# ESP32_adapter_revC.net
KiCad netlist of a schematic drawn in EAGLE
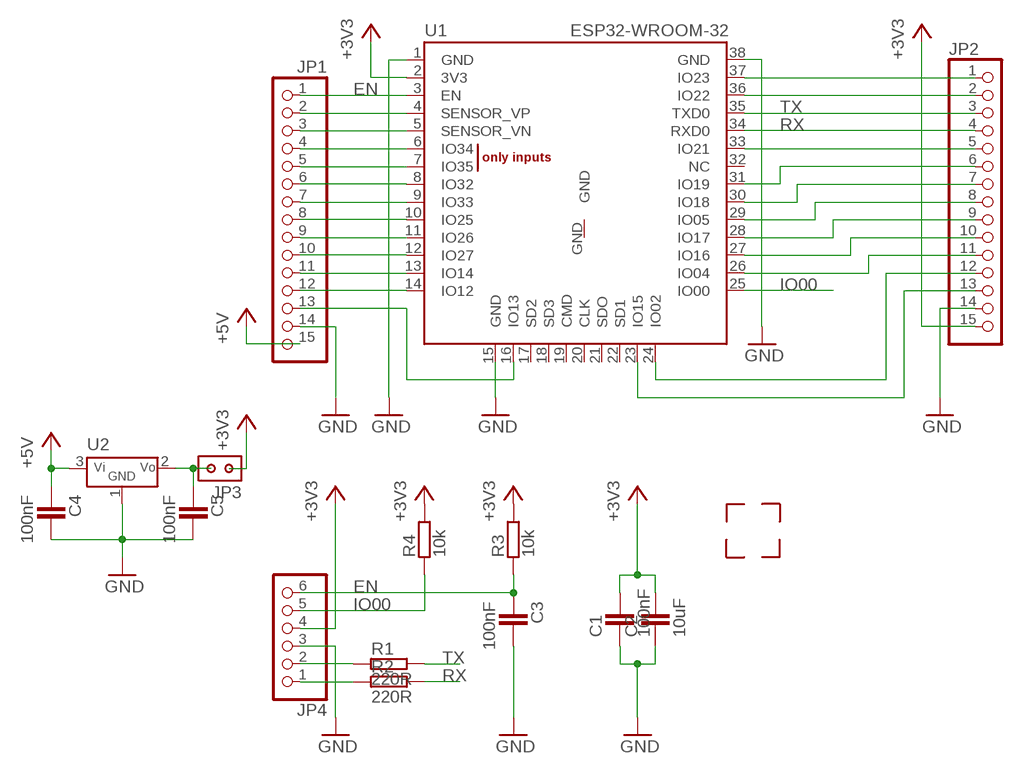
[diagram p0: schematic, sheet 1]

(export (version "E")
  (design (tool "Eeschema 10.0.6"))
  (components
    (comp (ref "C1")
      (value "100nF")
      (footprint "eagle-import:C0805")
      (libsource (lib "eagle-import") (part "C-CERAMIC'SMD'"))
    )
    (comp (ref "C2")
      (value "10uF")
      (footprint "eagle-import:C0805")
      (libsource (lib "eagle-import") (part "C-CERAMIC'SMD'"))
    )
    (comp (ref "C3")
      (value "100nF")
      (footprint "eagle-import:C0805")
      (libsource (lib "eagle-import") (part "C-CERAMIC'SMD'"))
    )
    (comp (ref "C4")
      (value "100nF")
      (footprint "eagle-import:C0805")
      (libsource (lib "eagle-import") (part "C-CERAMIC'SMD'"))
    )
    (comp (ref "C5")
      (value "100nF")
      (footprint "eagle-import:C0805")
      (libsource (lib "eagle-import") (part "C-CERAMIC'SMD'"))
    )
    (comp (ref "JP1")
      (value "PINHD-1X15")
      (footprint "eagle-import:1X15")
      (libsource (lib "eagle-import") (part "PINHD-1X15"))
    )
    (comp (ref "JP2")
      (value "PINHD-1X15")
      (footprint "eagle-import:1X15")
      (libsource (lib "eagle-import") (part "PINHD-1X15"))
    )
    (comp (ref "JP3")
      (value "PINHD-2X1")
      (footprint "eagle-import:PINHD-2X1")
      (libsource (lib "eagle-import") (part "PINHD-2X1"))
    )
    (comp (ref "JP4")
      (value "PINHD-1X6")
      (footprint "eagle-import:1X06")
      (libsource (lib "eagle-import") (part "PINHD-1X6"))
    )
    (comp (ref "R1")
      (value "220R")
      (footprint "eagle-import:R0805")
      (libsource (lib "eagle-import") (part "R'2'"))
    )
    (comp (ref "R2")
      (value "220R")
      (footprint "eagle-import:R0805")
      (libsource (lib "eagle-import") (part "R'2'"))
    )
    (comp (ref "R3")
      (value "10k")
      (footprint "eagle-import:R0805")
      (libsource (lib "eagle-import") (part "R'2'"))
    )
    (comp (ref "R4")
      (value "10k")
      (footprint "eagle-import:R0805")
      (libsource (lib "eagle-import") (part "R'2'"))
    )
    (comp (ref "U$1")
      (value "CORNER")
      (footprint "eagle-import:CORNER")
      (libsource (lib "eagle-import") (part "CORNER"))
    )
    (comp (ref "U$2")
      (value "CORNER")
      (footprint "eagle-import:CORNER")
      (libsource (lib "eagle-import") (part "CORNER"))
    )
    (comp (ref "U$3")
      (value "CORNER")
      (footprint "eagle-import:CORNER")
      (libsource (lib "eagle-import") (part "CORNER"))
    )
    (comp (ref "U$4")
      (value "CORNER")
      (footprint "eagle-import:CORNER")
      (libsource (lib "eagle-import") (part "CORNER"))
    )
    (comp (ref "U1")
      (value "ESP-WROOM-32")
      (footprint "eagle-import:ESP-WROOM-32")
      (libsource (lib "eagle-import") (part "ESP-WROOM-32"))
    )
    (comp (ref "U2")
      (value "V_STAB'TS1117'")
      (footprint "eagle-import:SOT223")
      (libsource (lib "eagle-import") (part "V_STAB'TS1117'"))
    )
  )
  (nets
    (net (code "1") (name "+3V3") (class "Default")
      (node (ref "C1") (pin "2") (pinfunction "P$2_2") (pintype "bidirectional"))
      (node (ref "C2") (pin "2") (pinfunction "P$2_2") (pintype "bidirectional"))
      (node (ref "JP2") (pin "15") (pinfunction "15_15") (pintype "passive"))
      (node (ref "JP3") (pin "2") (pinfunction "2_2") (pintype "bidirectional"))
      (node (ref "JP4") (pin "4") (pinfunction "4_4") (pintype "passive"))
      (node (ref "R3") (pin "2") (pinfunction "P$2_2") (pintype "bidirectional"))
      (node (ref "R4") (pin "2") (pinfunction "P$2_2") (pintype "bidirectional"))
      (node (ref "U1") (pin "2") (pinfunction "3V3_2") (pintype "bidirectional"))
    )
    (net (code "2") (name "+5V") (class "Default")
      (node (ref "C4") (pin "1") (pinfunction "P$1_1") (pintype "bidirectional"))
      (node (ref "JP1") (pin "15") (pinfunction "15_15") (pintype "passive"))
      (node (ref "U2") (pin "3") (pinfunction "VIN_3") (pintype "power_in"))
    )
    (net (code "3") (name "/EN") (class "Default")
      (node (ref "C3") (pin "1") (pinfunction "P$1_1") (pintype "bidirectional"))
      (node (ref "JP1") (pin "1") (pinfunction "1_1") (pintype "passive"))
      (node (ref "JP4") (pin "6") (pinfunction "6_6") (pintype "passive"))
      (node (ref "R3") (pin "1") (pinfunction "P$1_1") (pintype "bidirectional"))
      (node (ref "U1") (pin "3") (pinfunction "EN_3") (pintype "bidirectional"))
    )
    (net (code "4") (name "/IO00") (class "Default")
      (node (ref "JP4") (pin "5") (pinfunction "5_5") (pintype "passive"))
      (node (ref "R4") (pin "1") (pinfunction "P$1_1") (pintype "bidirectional"))
      (node (ref "U1") (pin "25") (pinfunction "IO00_25") (pintype "bidirectional"))
    )
    (net (code "5") (name "/RX") (class "Default")
      (node (ref "JP2") (pin "4") (pinfunction "4_4") (pintype "passive"))
      (node (ref "R2") (pin "2") (pinfunction "P$2_2") (pintype "bidirectional"))
      (node (ref "U1") (pin "34") (pinfunction "RXD0_34") (pintype "bidirectional"))
    )
    (net (code "6") (name "/TX") (class "Default")
      (node (ref "JP2") (pin "3") (pinfunction "3_3") (pintype "passive"))
      (node (ref "R1") (pin "2") (pinfunction "P$2_2") (pintype "bidirectional"))
      (node (ref "U1") (pin "35") (pinfunction "TXD0_35") (pintype "bidirectional"))
    )
    (net (code "7") (name "GND") (class "Default")
      (node (ref "C1") (pin "1") (pinfunction "P$1_1") (pintype "bidirectional"))
      (node (ref "C2") (pin "1") (pinfunction "P$1_1") (pintype "bidirectional"))
      (node (ref "C3") (pin "2") (pinfunction "P$2_2") (pintype "bidirectional"))
      (node (ref "C4") (pin "2") (pinfunction "P$2_2") (pintype "bidirectional"))
      (node (ref "C5") (pin "2") (pinfunction "P$2_2") (pintype "bidirectional"))
      (node (ref "JP1") (pin "14") (pinfunction "14_14") (pintype "passive"))
      (node (ref "JP2") (pin "14") (pinfunction "14_14") (pintype "passive"))
      (node (ref "JP4") (pin "3") (pinfunction "3_3") (pintype "passive"))
      (node (ref "U1") (pin "1") (pinfunction "GND_1") (pintype "bidirectional"))
      (node (ref "U1") (pin "15") (pinfunction "GND_15") (pintype "bidirectional"))
      (node (ref "U1") (pin "38") (pinfunction "GND_38") (pintype "bidirectional"))
      (node (ref "U2") (pin "1") (pinfunction "GND_1") (pintype "power_in"))
    )
    (net (code "8") (name "Net-(C5-P$1)") (class "Default")
      (node (ref "C5") (pin "1") (pinfunction "P$1_1") (pintype "bidirectional"))
      (node (ref "JP3") (pin "1") (pinfunction "1_1") (pintype "input"))
      (node (ref "U2") (pin "2") (pinfunction "VOUT_2") (pintype "power_in"))
    )
    (net (code "9") (name "Net-(R1-P$1)") (class "Default")
      (node (ref "JP4") (pin "2") (pinfunction "2_2") (pintype "passive"))
      (node (ref "R1") (pin "1") (pinfunction "P$1_1") (pintype "bidirectional"))
    )
    (net (code "10") (name "Net-(R2-P$1)") (class "Default")
      (node (ref "JP4") (pin "1") (pinfunction "1_1") (pintype "passive"))
      (node (ref "R2") (pin "1") (pinfunction "P$1_1") (pintype "bidirectional"))
    )
    (net (code "11") (name "Net-(U1-IO02)") (class "Default")
      (node (ref "JP2") (pin "12") (pinfunction "12_12") (pintype "passive"))
      (node (ref "U1") (pin "24") (pinfunction "IO02_24") (pintype "bidirectional"))
    )
    (net (code "12") (name "Net-(U1-IO04)") (class "Default")
      (node (ref "JP2") (pin "11") (pinfunction "11_11") (pintype "passive"))
      (node (ref "U1") (pin "26") (pinfunction "IO04_26") (pintype "bidirectional"))
    )
    (net (code "13") (name "Net-(U1-IO05)") (class "Default")
      (node (ref "JP2") (pin "8") (pinfunction "8_8") (pintype "passive"))
      (node (ref "U1") (pin "29") (pinfunction "IO05_29") (pintype "bidirectional"))
    )
    (net (code "14") (name "Net-(U1-IO12)") (class "Default")
      (node (ref "JP1") (pin "12") (pinfunction "12_12") (pintype "passive"))
      (node (ref "U1") (pin "14") (pinfunction "IO12_14") (pintype "bidirectional"))
    )
    (net (code "15") (name "Net-(U1-IO13)") (class "Default")
      (node (ref "JP1") (pin "13") (pinfunction "13_13") (pintype "passive"))
      (node (ref "U1") (pin "16") (pinfunction "IO13_16") (pintype "bidirectional"))
    )
    (net (code "16") (name "Net-(U1-IO14)") (class "Default")
      (node (ref "JP1") (pin "11") (pinfunction "11_11") (pintype "passive"))
      (node (ref "U1") (pin "13") (pinfunction "IO14_13") (pintype "bidirectional"))
    )
    (net (code "17") (name "Net-(U1-IO15)") (class "Default")
      (node (ref "JP2") (pin "13") (pinfunction "13_13") (pintype "passive"))
      (node (ref "U1") (pin "23") (pinfunction "IO15_23") (pintype "bidirectional"))
    )
    (net (code "18") (name "Net-(U1-IO16)") (class "Default")
      (node (ref "JP2") (pin "10") (pinfunction "10_10") (pintype "passive"))
      (node (ref "U1") (pin "27") (pinfunction "IO16_27") (pintype "bidirectional"))
    )
    (net (code "19") (name "Net-(U1-IO17)") (class "Default")
      (node (ref "JP2") (pin "9") (pinfunction "9_9") (pintype "passive"))
      (node (ref "U1") (pin "28") (pinfunction "IO17_28") (pintype "bidirectional"))
    )
    (net (code "20") (name "Net-(U1-IO18)") (class "Default")
      (node (ref "JP2") (pin "7") (pinfunction "7_7") (pintype "passive"))
      (node (ref "U1") (pin "30") (pinfunction "IO18_30") (pintype "bidirectional"))
    )
    (net (code "21") (name "Net-(U1-IO19)") (class "Default")
      (node (ref "JP2") (pin "6") (pinfunction "6_6") (pintype "passive"))
      (node (ref "U1") (pin "31") (pinfunction "IO19_31") (pintype "bidirectional"))
    )
    (net (code "22") (name "Net-(U1-IO21)") (class "Default")
      (node (ref "JP2") (pin "5") (pinfunction "5_5") (pintype "passive"))
      (node (ref "U1") (pin "33") (pinfunction "IO21_33") (pintype "bidirectional"))
    )
    (net (code "23") (name "Net-(U1-IO22)") (class "Default")
      (node (ref "JP2") (pin "2") (pinfunction "2_2") (pintype "passive"))
      (node (ref "U1") (pin "36") (pinfunction "IO22_36") (pintype "bidirectional"))
    )
    (net (code "24") (name "Net-(U1-IO23)") (class "Default")
      (node (ref "JP2") (pin "1") (pinfunction "1_1") (pintype "passive"))
      (node (ref "U1") (pin "37") (pinfunction "IO23_37") (pintype "bidirectional"))
    )
    (net (code "25") (name "Net-(U1-IO25)") (class "Default")
      (node (ref "JP1") (pin "8") (pinfunction "8_8") (pintype "passive"))
      (node (ref "U1") (pin "10") (pinfunction "IO25_10") (pintype "bidirectional"))
    )
    (net (code "26") (name "Net-(U1-IO26)") (class "Default")
      (node (ref "JP1") (pin "9") (pinfunction "9_9") (pintype "passive"))
      (node (ref "U1") (pin "11") (pinfunction "IO26_11") (pintype "bidirectional"))
    )
    (net (code "27") (name "Net-(U1-IO27)") (class "Default")
      (node (ref "JP1") (pin "10") (pinfunction "10_10") (pintype "passive"))
      (node (ref "U1") (pin "12") (pinfunction "IO27_12") (pintype "bidirectional"))
    )
    (net (code "28") (name "Net-(U1-IO32)") (class "Default")
      (node (ref "JP1") (pin "6") (pinfunction "6_6") (pintype "passive"))
      (node (ref "U1") (pin "8") (pinfunction "IO32_8") (pintype "bidirectional"))
    )
    (net (code "29") (name "Net-(U1-IO33)") (class "Default")
      (node (ref "JP1") (pin "7") (pinfunction "7_7") (pintype "passive"))
      (node (ref "U1") (pin "9") (pinfunction "IO33_9") (pintype "bidirectional"))
    )
    (net (code "30") (name "Net-(U1-IO34)") (class "Default")
      (node (ref "JP1") (pin "4") (pinfunction "4_4") (pintype "passive"))
      (node (ref "U1") (pin "6") (pinfunction "IO34_6") (pintype "input"))
    )
    (net (code "31") (name "Net-(U1-IO35)") (class "Default")
      (node (ref "JP1") (pin "5") (pinfunction "5_5") (pintype "passive"))
      (node (ref "U1") (pin "7") (pinfunction "IO35_7") (pintype "input"))
    )
    (net (code "32") (name "Net-(U1-SENSOR_VN)") (class "Default")
      (node (ref "JP1") (pin "3") (pinfunction "3_3") (pintype "passive"))
      (node (ref "U1") (pin "5") (pinfunction "SENSOR_VN_5") (pintype "input"))
    )
    (net (code "33") (name "Net-(U1-SENSOR_VP)") (class "Default")
      (node (ref "JP1") (pin "2") (pinfunction "2_2") (pintype "passive"))
      (node (ref "U1") (pin "4") (pinfunction "SENSOR_VP_4") (pintype "input"))
    )
    (net (code "34") (name "unconnected-(U1-CLK-Pad20)") (class "Default")
      (node (ref "U1") (pin "20") (pinfunction "CLK_20") (pintype "bidirectional"))
    )
    (net (code "35") (name "unconnected-(U1-CMD-Pad19)") (class "Default")
      (node (ref "U1") (pin "19") (pinfunction "CMD_19") (pintype "bidirectional"))
    )
    (net (code "36") (name "unconnected-(U1-NC-Pad32)") (class "Default")
      (node (ref "U1") (pin "32") (pinfunction "NC_32") (pintype "bidirectional"))
    )
    (net (code "37") (name "unconnected-(U1-PadGND)") (class "Default")
      (node (ref "U1") (pin "GND") (pinfunction "GND_GND") (pintype "bidirectional"))
    )
    (net (code "38") (name "unconnected-(U1-SD1-Pad22)") (class "Default")
      (node (ref "U1") (pin "22") (pinfunction "SD1_22") (pintype "bidirectional"))
    )
    (net (code "39") (name "unconnected-(U1-SD2-Pad17)") (class "Default")
      (node (ref "U1") (pin "17") (pinfunction "SD2_17") (pintype "bidirectional"))
    )
    (net (code "40") (name "unconnected-(U1-SD3-Pad18)") (class "Default")
      (node (ref "U1") (pin "18") (pinfunction "SD3_18") (pintype "bidirectional"))
    )
    (net (code "41") (name "unconnected-(U1-SDO-Pad21)") (class "Default")
      (node (ref "U1") (pin "21") (pinfunction "SDO_21") (pintype "bidirectional"))
    )
  )
)
